# B293A_ADC.net
KiCad netlist of a schematic drawn in Altium Designer
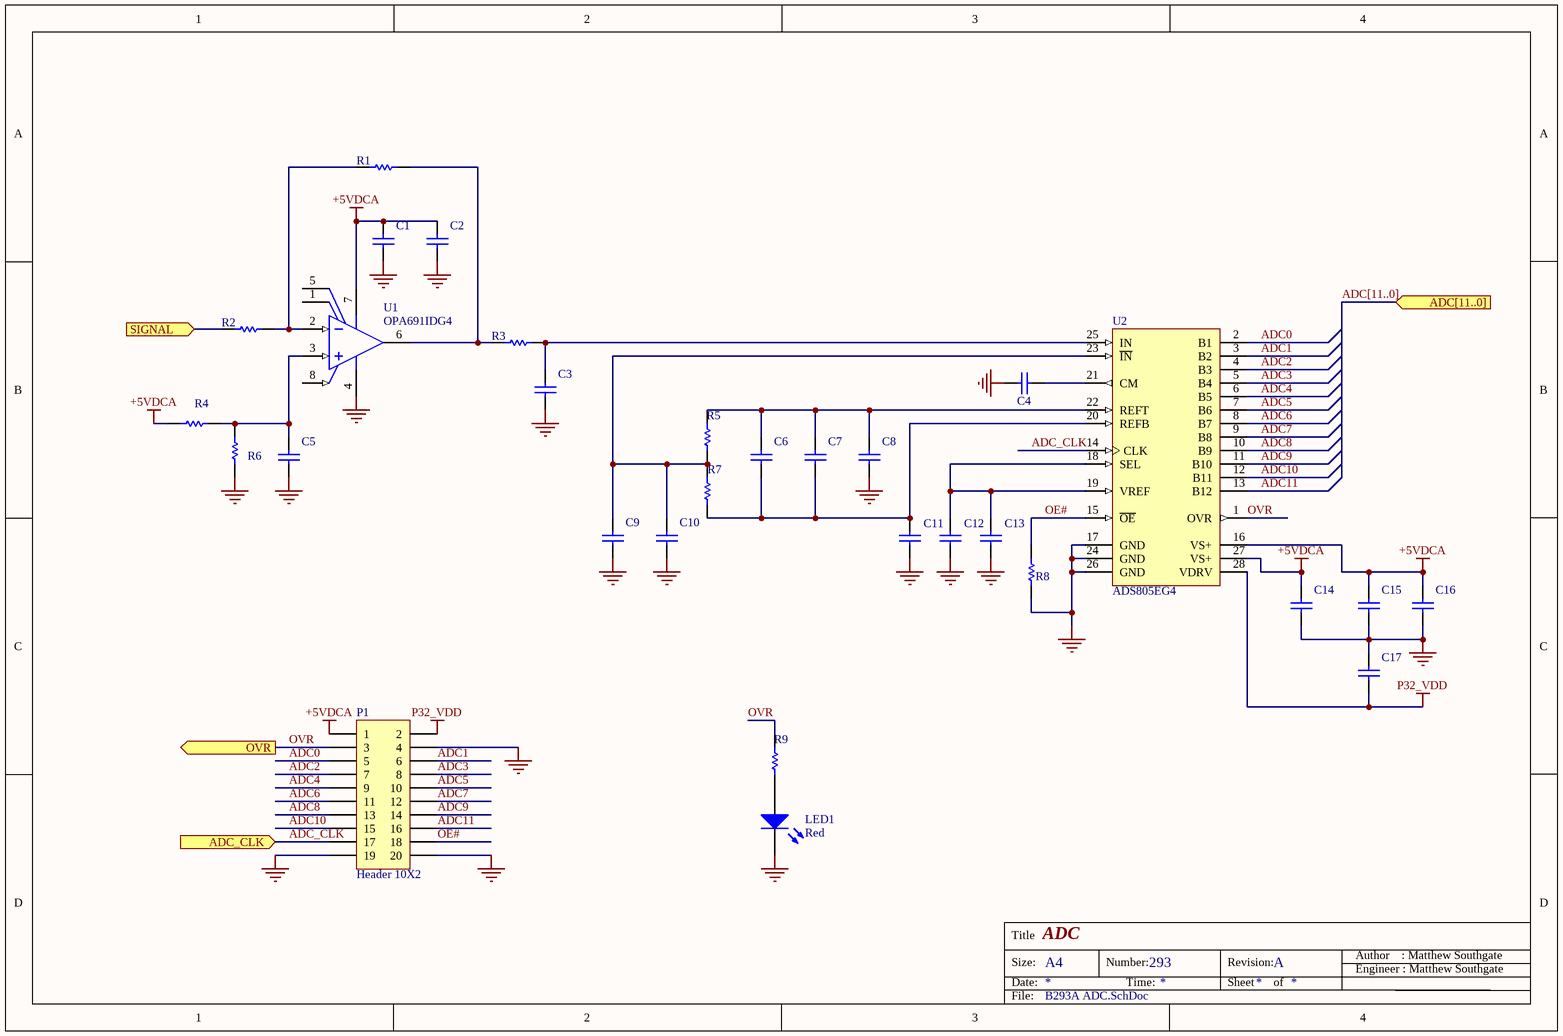
[diagram p0: B293A ADC.SchDoc]

(export (version "E")
  (design (tool "Eeschema 10.0.6"))
  (components
    (comp (ref "C1")
      (value "CAP 100nF 50V 0805(2012)")
      (footprint "CAPC0805(2012)75_L")
      (description "CAP 100nF 50V ±20% 0805 (2012 Metric) Thickness 0.75mm SMD")
      (fields (field (name "TOLERANCE") "±20%"))
      (libsource (lib "Altium Content Vault") (part "CAP"))
    )
    (comp (ref "C2")
      (value "CAP 10uF 25V 0805(2012)")
      (footprint "CAPC0805(2012)145_N")
      (description "CAP 10uF 25V ±20% 0805 (2012 Metric) Thickness 1.45mm SMD")
      (fields (field (name "TOLERANCE") "±20%"))
      (libsource (lib "Altium Content Vault") (part "CAP"))
    )
    (comp (ref "C3")
      (value "CAP 1.5nF 50V 0805(2012)")
      (footprint "CAPC0805(2012)75_M")
      (description "CAP 1.5nF 50V ±10% 0805 (2012 Metric) Thickness 0.75mm SMD")
      (fields (field (name "TOLERANCE") "±10%"))
      (libsource (lib "Altium Content Vault") (part "CAP"))
    )
    (comp (ref "C4")
      (value "CAP 100nF 50V 0805(2012)")
      (footprint "CAPC0805(2012)75_L")
      (description "CAP 100nF 50V ±20% 0805 (2012 Metric) Thickness 0.75mm SMD")
      (fields (field (name "TOLERANCE") "±20%"))
      (libsource (lib "Altium Content Vault") (part "CAP"))
    )
    (comp (ref "C5")
      (value "CAP 100nF 50V 0805(2012)")
      (footprint "CAPC0805(2012)75_L")
      (description "CAP 100nF 50V ±20% 0805 (2012 Metric) Thickness 0.75mm SMD")
      (fields (field (name "TOLERANCE") "±20%"))
      (libsource (lib "Altium Content Vault") (part "CAP"))
    )
    (comp (ref "C6")
      (value "CAP 10uF 25V 0805(2012)")
      (footprint "CAPC0805(2012)145_N")
      (description "CAP 10uF 25V ±20% 0805 (2012 Metric) Thickness 1.45mm SMD")
      (fields (field (name "TOLERANCE") "±20%"))
      (libsource (lib "Altium Content Vault") (part "CAP"))
    )
    (comp (ref "C7")
      (value "CAP 100nF 50V 0805(2012)")
      (footprint "CAPC0805(2012)75_L")
      (description "CAP 100nF 50V ±20% 0805 (2012 Metric) Thickness 0.75mm SMD")
      (fields (field (name "TOLERANCE") "±20%"))
      (libsource (lib "Altium Content Vault") (part "CAP"))
    )
    (comp (ref "C8")
      (value "CAP 100nF 50V 0805(2012)")
      (footprint "CAPC0805(2012)75_L")
      (description "CAP 100nF 50V ±20% 0805 (2012 Metric) Thickness 0.75mm SMD")
      (fields (field (name "TOLERANCE") "±20%"))
      (libsource (lib "Altium Content Vault") (part "CAP"))
    )
    (comp (ref "C9")
      (value "CAP 10uF 25V 0805(2012)")
      (footprint "CAPC0805(2012)145_N")
      (description "CAP 10uF 25V ±20% 0805 (2012 Metric) Thickness 1.45mm SMD")
      (fields (field (name "TOLERANCE") "±20%"))
      (libsource (lib "Altium Content Vault") (part "CAP"))
    )
    (comp (ref "C10")
      (value "CAP 100nF 50V 0805(2012)")
      (footprint "CAPC0805(2012)75_L")
      (description "CAP 100nF 50V ±20% 0805 (2012 Metric) Thickness 0.75mm SMD")
      (fields (field (name "TOLERANCE") "±20%"))
      (libsource (lib "Altium Content Vault") (part "CAP"))
    )
    (comp (ref "C11")
      (value "CAP 100nF 50V 0805(2012)")
      (footprint "CAPC0805(2012)75_L")
      (description "CAP 100nF 50V ±20% 0805 (2012 Metric) Thickness 0.75mm SMD")
      (fields (field (name "TOLERANCE") "±20%"))
      (libsource (lib "Altium Content Vault") (part "CAP"))
    )
    (comp (ref "C12")
      (value "CAP 10uF 25V 0805(2012)")
      (footprint "CAPC0805(2012)145_N")
      (description "CAP 10uF 25V ±20% 0805 (2012 Metric) Thickness 1.45mm SMD")
      (fields (field (name "TOLERANCE") "±20%"))
      (libsource (lib "Altium Content Vault") (part "CAP"))
    )
    (comp (ref "C13")
      (value "CAP 100nF 50V 0805(2012)")
      (footprint "CAPC0805(2012)75_L")
      (description "CAP 100nF 50V ±20% 0805 (2012 Metric) Thickness 0.75mm SMD")
      (fields (field (name "TOLERANCE") "±20%"))
      (libsource (lib "Altium Content Vault") (part "CAP"))
    )
    (comp (ref "C14")
      (value "CAP 100nF 50V 0805(2012)")
      (footprint "CAPC0805(2012)75_L")
      (description "CAP 100nF 50V ±20% 0805 (2012 Metric) Thickness 0.75mm SMD")
      (fields (field (name "TOLERANCE") "±20%"))
      (libsource (lib "Altium Content Vault") (part "CAP"))
    )
    (comp (ref "C15")
      (value "CAP 100nF 50V 0805(2012)")
      (footprint "CAPC0805(2012)75_L")
      (description "CAP 100nF 50V ±20% 0805 (2012 Metric) Thickness 0.75mm SMD")
      (fields (field (name "TOLERANCE") "±20%"))
      (libsource (lib "Altium Content Vault") (part "CAP"))
    )
    (comp (ref "C16")
      (value "CAP 2.2uF 50V 0805(2012)")
      (footprint "CAPC0805(2012)145_M")
      (description "CAP 2.2uF 50V ±10% 0805 (2012 Metric) Thickness 1.45mm SMD")
      (fields (field (name "TOLERANCE") "±10%"))
      (libsource (lib "Altium Content Vault") (part "CAP"))
    )
    (comp (ref "C17")
      (value "CAP 100nF 50V 0805(2012)")
      (footprint "CAPC0805(2012)75_L")
      (description "CAP 100nF 50V ±20% 0805 (2012 Metric) Thickness 0.75mm SMD")
      (fields (field (name "TOLERANCE") "±20%"))
      (libsource (lib "Altium Content Vault") (part "CAP"))
    )
    (comp (ref "LED1")
      (value "Red")
      (footprint "Matt PCB Library:1206 - LED")
      (description "LED, ALINGAP, SMD, 1206, RED")
      (fields
        (field (name "MANUFACTURER PART NUMBER") "KPC-3216SURCK")
        (field (name "MANUFACTURER") "KINGBRIGHT")
      )
      (libsource (lib "Matt SCH Library") (part "LED 1206 RED"))
    )
    (comp (ref "P1")
      (value "Header 10X2")
      (footprint "HDR2X10")
      (description "Header, 10-Pin, Dual row")
      (fields (field (name "PUBLISHER") "Altium Limited"))
      (libsource (lib "Miscellaneous Connectors") (part "Header 10X2"))
    )
    (comp (ref "R1")
      (value "1K8 5% 0805(2012)")
      (footprint "RESC0805(2012)_N")
      (description "1K8 0.125W 5% 0805 (2012 Metric)  SMD")
      (fields (field (name "TOLERANCE") "5 %") (field (name "POWER") "0.125 W"))
      (libsource (lib "Altium Content Vault") (part "RES"))
    )
    (comp (ref "R2")
      (value "1K8 5% 0805(2012)")
      (footprint "RESC0805(2012)_N")
      (description "1K8 0.125W 5% 0805 (2012 Metric)  SMD")
      (fields (field (name "TOLERANCE") "5 %") (field (name "POWER") "0.125 W"))
      (libsource (lib "Altium Content Vault") (part "RES"))
    )
    (comp (ref "R3")
      (value "47R 5% 0805(2012)")
      (footprint "RESC0805(2012)_M")
      (description "47R 0.125W 5% 0805 (2012 Metric)  SMD")
      (fields (field (name "TOLERANCE") "5 %") (field (name "POWER") "0.125 W"))
      (libsource (lib "Altium Content Vault") (part "RES"))
    )
    (comp (ref "R4")
      (value "1K8 5% 0805(2012)")
      (footprint "RESC0805(2012)_N")
      (description "1K8 0.125W 5% 0805 (2012 Metric)  SMD")
      (fields (field (name "TOLERANCE") "5 %") (field (name "POWER") "0.125 W"))
      (libsource (lib "Altium Content Vault") (part "RES"))
    )
    (comp (ref "R5")
      (value "1K8 5% 0805(2012)")
      (footprint "RESC0805(2012)_N")
      (description "1K8 0.125W 5% 0805 (2012 Metric)  SMD")
      (fields (field (name "TOLERANCE") "5 %") (field (name "POWER") "0.125 W"))
      (libsource (lib "Altium Content Vault") (part "RES"))
    )
    (comp (ref "R6")
      (value "680R 1% 0805(2012)")
      (footprint "RESC0805(2012)_L")
      (description "680R 0.125W 1% 0805 (2012 Metric)  SMD")
      (fields (field (name "TOLERANCE") "1 %") (field (name "POWER") "0.125 W"))
      (libsource (lib "Altium Content Vault") (part "RES"))
    )
    (comp (ref "R7")
      (value "1K8 5% 0805(2012)")
      (footprint "RESC0805(2012)_N")
      (description "1K8 0.125W 5% 0805 (2012 Metric)  SMD")
      (fields (field (name "TOLERANCE") "5 %") (field (name "POWER") "0.125 W"))
      (libsource (lib "Altium Content Vault") (part "RES"))
    )
    (comp (ref "R8")
      (value "10K 1% 0805(2012)")
      (footprint "RESC0805(2012)_M")
      (description "10K 0.125W 1% 0805 (2012 Metric)  SMD")
      (fields (field (name "POWER") "0.125 W") (field (name "TOLERANCE") "1 %"))
      (libsource (lib "Altium Content Vault") (part "RES"))
    )
    (comp (ref "R9")
      (value "1K 5% 0805(2012)")
      (footprint "RESC0805(2012)_N")
      (description "1K 0.125W 5% 0805 (2012 Metric)  SMD")
      (fields (field (name "TOLERANCE") "5 %") (field (name "POWER") "0.125 W"))
      (libsource (lib "Altium Content Vault") (part "RES"))
    )
    (comp (ref "U1")
      (value "OPA691IDG4")
      (footprint "TI-D8_N")
      (fields (field (name "MANUFACTURER") "Texas Instruments"))
      (libsource (lib "Altium Content Vault") (part "TI-AMP-S4-2-8"))
    )
    (comp (ref "U2")
      (value "ADS805EG4")
      (footprint "TI-DB28_M")
      (fields (field (name "MANUFACTURER") "Texas Instruments"))
      (libsource (lib "Altium Content Vault") (part "TI-ADS805DB28"))
    )
  )
  (nets
    (net (code "1") (name "+5VDCA") (class "Default")
      (node (ref "C1") (pin "2") (pinfunction "2_2") (pintype "passive"))
      (node (ref "C14") (pin "2") (pinfunction "2_2") (pintype "passive"))
      (node (ref "C15") (pin "2") (pinfunction "2_2") (pintype "passive"))
      (node (ref "C16") (pin "2") (pinfunction "2_2") (pintype "passive"))
      (node (ref "C2") (pin "2") (pinfunction "2_2") (pintype "passive"))
      (node (ref "P1") (pin "1") (pinfunction "1_1") (pintype "passive"))
      (node (ref "R4") (pin "1") (pinfunction "1_1") (pintype "passive"))
      (node (ref "U1") (pin "7") (pinfunction "VS+_7") (pintype "power_in"))
      (node (ref "U2") (pin "16") (pinfunction "VS+_16") (pintype "power_in"))
      (node (ref "U2") (pin "27") (pinfunction "VS+_27") (pintype "power_in"))
    )
    (net (code "2") (name "/ADC0") (class "Default")
      (node (ref "P1") (pin "5") (pinfunction "5_5") (pintype "passive"))
      (node (ref "U2") (pin "2") (pinfunction "B1_2") (pintype "tri_state"))
    )
    (net (code "3") (name "/ADC1") (class "Default")
      (node (ref "P1") (pin "6") (pinfunction "6_6") (pintype "passive"))
      (node (ref "U2") (pin "3") (pinfunction "B2_3") (pintype "tri_state"))
    )
    (net (code "4") (name "/ADC2") (class "Default")
      (node (ref "P1") (pin "7") (pinfunction "7_7") (pintype "passive"))
      (node (ref "U2") (pin "4") (pinfunction "B3_4") (pintype "tri_state"))
    )
    (net (code "5") (name "/ADC3") (class "Default")
      (node (ref "P1") (pin "8") (pinfunction "8_8") (pintype "passive"))
      (node (ref "U2") (pin "5") (pinfunction "B4_5") (pintype "tri_state"))
    )
    (net (code "6") (name "/ADC4") (class "Default")
      (node (ref "P1") (pin "9") (pinfunction "9_9") (pintype "passive"))
      (node (ref "U2") (pin "6") (pinfunction "B5_6") (pintype "tri_state"))
    )
    (net (code "7") (name "/ADC5") (class "Default")
      (node (ref "P1") (pin "10") (pinfunction "10_10") (pintype "passive"))
      (node (ref "U2") (pin "7") (pinfunction "B6_7") (pintype "tri_state"))
    )
    (net (code "8") (name "/ADC6") (class "Default")
      (node (ref "P1") (pin "11") (pinfunction "11_11") (pintype "passive"))
      (node (ref "U2") (pin "8") (pinfunction "B7_8") (pintype "tri_state"))
    )
    (net (code "9") (name "/ADC7") (class "Default")
      (node (ref "P1") (pin "12") (pinfunction "12_12") (pintype "passive"))
      (node (ref "U2") (pin "9") (pinfunction "B8_9") (pintype "tri_state"))
    )
    (net (code "10") (name "/ADC8") (class "Default")
      (node (ref "P1") (pin "13") (pinfunction "13_13") (pintype "passive"))
      (node (ref "U2") (pin "10") (pinfunction "B9_10") (pintype "tri_state"))
    )
    (net (code "11") (name "/ADC9") (class "Default")
      (node (ref "P1") (pin "14") (pinfunction "14_14") (pintype "passive"))
      (node (ref "U2") (pin "11") (pinfunction "B10_11") (pintype "tri_state"))
    )
    (net (code "12") (name "/ADC10") (class "Default")
      (node (ref "P1") (pin "15") (pinfunction "15_15") (pintype "passive"))
      (node (ref "U2") (pin "12") (pinfunction "B11_12") (pintype "tri_state"))
    )
    (net (code "13") (name "/ADC11") (class "Default")
      (node (ref "P1") (pin "16") (pinfunction "16_16") (pintype "passive"))
      (node (ref "U2") (pin "13") (pinfunction "B12_13") (pintype "tri_state"))
    )
    (net (code "15") (name "/ADC_CLK") (class "Default")
      (node (ref "P1") (pin "17") (pinfunction "17_17") (pintype "passive"))
      (node (ref "U2") (pin "14") (pinfunction "CLK_14") (pintype "input"))
    )
    (net (code "16") (name "/OE#") (class "Default")
      (node (ref "P1") (pin "18") (pinfunction "18_18") (pintype "passive"))
      (node (ref "R8") (pin "1") (pinfunction "1_1") (pintype "passive"))
      (node (ref "U2") (pin "15") (pinfunction "~{OE}_15") (pintype "input"))
    )
    (net (code "17") (name "/OVR") (class "Default")
      (node (ref "P1") (pin "3") (pinfunction "3_3") (pintype "passive"))
      (node (ref "R9") (pin "2") (pinfunction "2_2") (pintype "passive"))
      (node (ref "U2") (pin "1") (pinfunction "OVR_1") (pintype "output"))
    )
    (net (code "18") (name "/SIGNAL") (class "Default")
      (node (ref "R2") (pin "2") (pinfunction "2_2") (pintype "passive"))
    )
    (net (code "19") (name "GND") (class "Default")
      (node (ref "C1") (pin "1") (pinfunction "1_1") (pintype "passive"))
      (node (ref "C10") (pin "1") (pinfunction "1_1") (pintype "passive"))
      (node (ref "C11") (pin "1") (pinfunction "1_1") (pintype "passive"))
      (node (ref "C12") (pin "1") (pinfunction "1_1") (pintype "passive"))
      (node (ref "C13") (pin "1") (pinfunction "1_1") (pintype "passive"))
      (node (ref "C14") (pin "1") (pinfunction "1_1") (pintype "passive"))
      (node (ref "C15") (pin "1") (pinfunction "1_1") (pintype "passive"))
      (node (ref "C16") (pin "1") (pinfunction "1_1") (pintype "passive"))
      (node (ref "C17") (pin "2") (pinfunction "2_2") (pintype "passive"))
      (node (ref "C2") (pin "1") (pinfunction "1_1") (pintype "passive"))
      (node (ref "C3") (pin "1") (pinfunction "1_1") (pintype "passive"))
      (node (ref "C4") (pin "1") (pinfunction "1_1") (pintype "passive"))
      (node (ref "C5") (pin "1") (pinfunction "1_1") (pintype "passive"))
      (node (ref "C8") (pin "1") (pinfunction "1_1") (pintype "passive"))
      (node (ref "C9") (pin "1") (pinfunction "1_1") (pintype "passive"))
      (node (ref "LED1") (pin "K") (pinfunction "K_K") (pintype "passive"))
      (node (ref "P1") (pin "19") (pinfunction "19_19") (pintype "passive"))
      (node (ref "P1") (pin "20") (pinfunction "20_20") (pintype "passive"))
      (node (ref "P1") (pin "4") (pinfunction "4_4") (pintype "passive"))
      (node (ref "R6") (pin "2") (pinfunction "2_2") (pintype "passive"))
      (node (ref "R8") (pin "2") (pinfunction "2_2") (pintype "passive"))
      (node (ref "U1") (pin "4") (pinfunction "VS-_4") (pintype "power_in"))
      (node (ref "U2") (pin "17") (pinfunction "GND_17") (pintype "power_in"))
      (node (ref "U2") (pin "24") (pinfunction "GND_24") (pintype "power_in"))
      (node (ref "U2") (pin "26") (pinfunction "GND_26") (pintype "power_in"))
    )
    (net (code "20") (name "Net-(LED1-PadA)") (class "Default")
      (node (ref "LED1") (pin "A") (pinfunction "A_A") (pintype "passive"))
      (node (ref "R9") (pin "1") (pinfunction "1_1") (pintype "passive"))
    )
    (net (code "21") (name "Net-(U1-IN+)") (class "Default")
      (node (ref "C5") (pin "2") (pinfunction "2_2") (pintype "passive"))
      (node (ref "R4") (pin "2") (pinfunction "2_2") (pintype "passive"))
      (node (ref "R6") (pin "1") (pinfunction "1_1") (pintype "passive"))
      (node (ref "U1") (pin "3") (pinfunction "IN+_3") (pintype "input"))
    )
    (net (code "22") (name "Net-(U1-IN-)") (class "Default")
      (node (ref "R1") (pin "2") (pinfunction "2_2") (pintype "passive"))
      (node (ref "R2") (pin "1") (pinfunction "1_1") (pintype "passive"))
      (node (ref "U1") (pin "2") (pinfunction "IN-_2") (pintype "input"))
    )
    (net (code "23") (name "Net-(U1-OUT)") (class "Default")
      (node (ref "R1") (pin "1") (pinfunction "1_1") (pintype "passive"))
      (node (ref "R3") (pin "2") (pinfunction "2_2") (pintype "passive"))
      (node (ref "U1") (pin "6") (pinfunction "OUT_6") (pintype "tri_state"))
    )
    (net (code "24") (name "Net-(U2-CM)") (class "Default")
      (node (ref "C4") (pin "2") (pinfunction "2_2") (pintype "passive"))
      (node (ref "U2") (pin "21") (pinfunction "CM_21") (pintype "output"))
    )
    (net (code "25") (name "Net-(U2-IN)") (class "Default")
      (node (ref "C3") (pin "2") (pinfunction "2_2") (pintype "passive"))
      (node (ref "R3") (pin "1") (pinfunction "1_1") (pintype "passive"))
      (node (ref "U2") (pin "25") (pinfunction "IN_25") (pintype "input"))
    )
    (net (code "26") (name "Net-(U2-REFB)") (class "Default")
      (node (ref "C11") (pin "2") (pinfunction "2_2") (pintype "passive"))
      (node (ref "C6") (pin "1") (pinfunction "1_1") (pintype "passive"))
      (node (ref "C7") (pin "1") (pinfunction "1_1") (pintype "passive"))
      (node (ref "R7") (pin "1") (pinfunction "1_1") (pintype "passive"))
      (node (ref "U2") (pin "20") (pinfunction "REFB_20") (pintype "input"))
    )
    (net (code "27") (name "Net-(U2-REFT)") (class "Default")
      (node (ref "C6") (pin "2") (pinfunction "2_2") (pintype "passive"))
      (node (ref "C7") (pin "2") (pinfunction "2_2") (pintype "passive"))
      (node (ref "C8") (pin "2") (pinfunction "2_2") (pintype "passive"))
      (node (ref "R5") (pin "2") (pinfunction "2_2") (pintype "passive"))
      (node (ref "U2") (pin "22") (pinfunction "REFT_22") (pintype "input"))
    )
    (net (code "28") (name "Net-(U2-SEL)") (class "Default")
      (node (ref "C12") (pin "2") (pinfunction "2_2") (pintype "passive"))
      (node (ref "C13") (pin "2") (pinfunction "2_2") (pintype "passive"))
      (node (ref "U2") (pin "18") (pinfunction "SEL_18") (pintype "input"))
      (node (ref "U2") (pin "19") (pinfunction "VREF_19") (pintype "input"))
    )
    (net (code "29") (name "Net-(U2-~{IN})") (class "Default")
      (node (ref "C10") (pin "2") (pinfunction "2_2") (pintype "passive"))
      (node (ref "C9") (pin "2") (pinfunction "2_2") (pintype "passive"))
      (node (ref "R5") (pin "1") (pinfunction "1_1") (pintype "passive"))
      (node (ref "R7") (pin "2") (pinfunction "2_2") (pintype "passive"))
      (node (ref "U2") (pin "23") (pinfunction "~{IN}_23") (pintype "input"))
    )
    (net (code "30") (name "P32_VDD") (class "Default")
      (node (ref "C17") (pin "1") (pinfunction "1_1") (pintype "passive"))
      (node (ref "P1") (pin "2") (pinfunction "2_2") (pintype "passive"))
      (node (ref "U2") (pin "28") (pinfunction "VDRV_28") (pintype "power_in"))
    )
    (net (code "31") (name "unconnected-(U1-NC-Pad1)") (class "Default")
      (node (ref "U1") (pin "1") (pinfunction "NC_1") (pintype "passive"))
    )
    (net (code "32") (name "unconnected-(U1-NC-Pad5)") (class "Default")
      (node (ref "U1") (pin "5") (pinfunction "NC_5") (pintype "passive"))
    )
    (net (code "33") (name "unconnected-(U1-~{DIS}-Pad8)") (class "Default")
      (node (ref "U1") (pin "8") (pinfunction "~{DIS}_8") (pintype "input"))
    )
  )
)
